# IronSAMD51.net
KiCad netlist of a schematic drawn in EAGLE
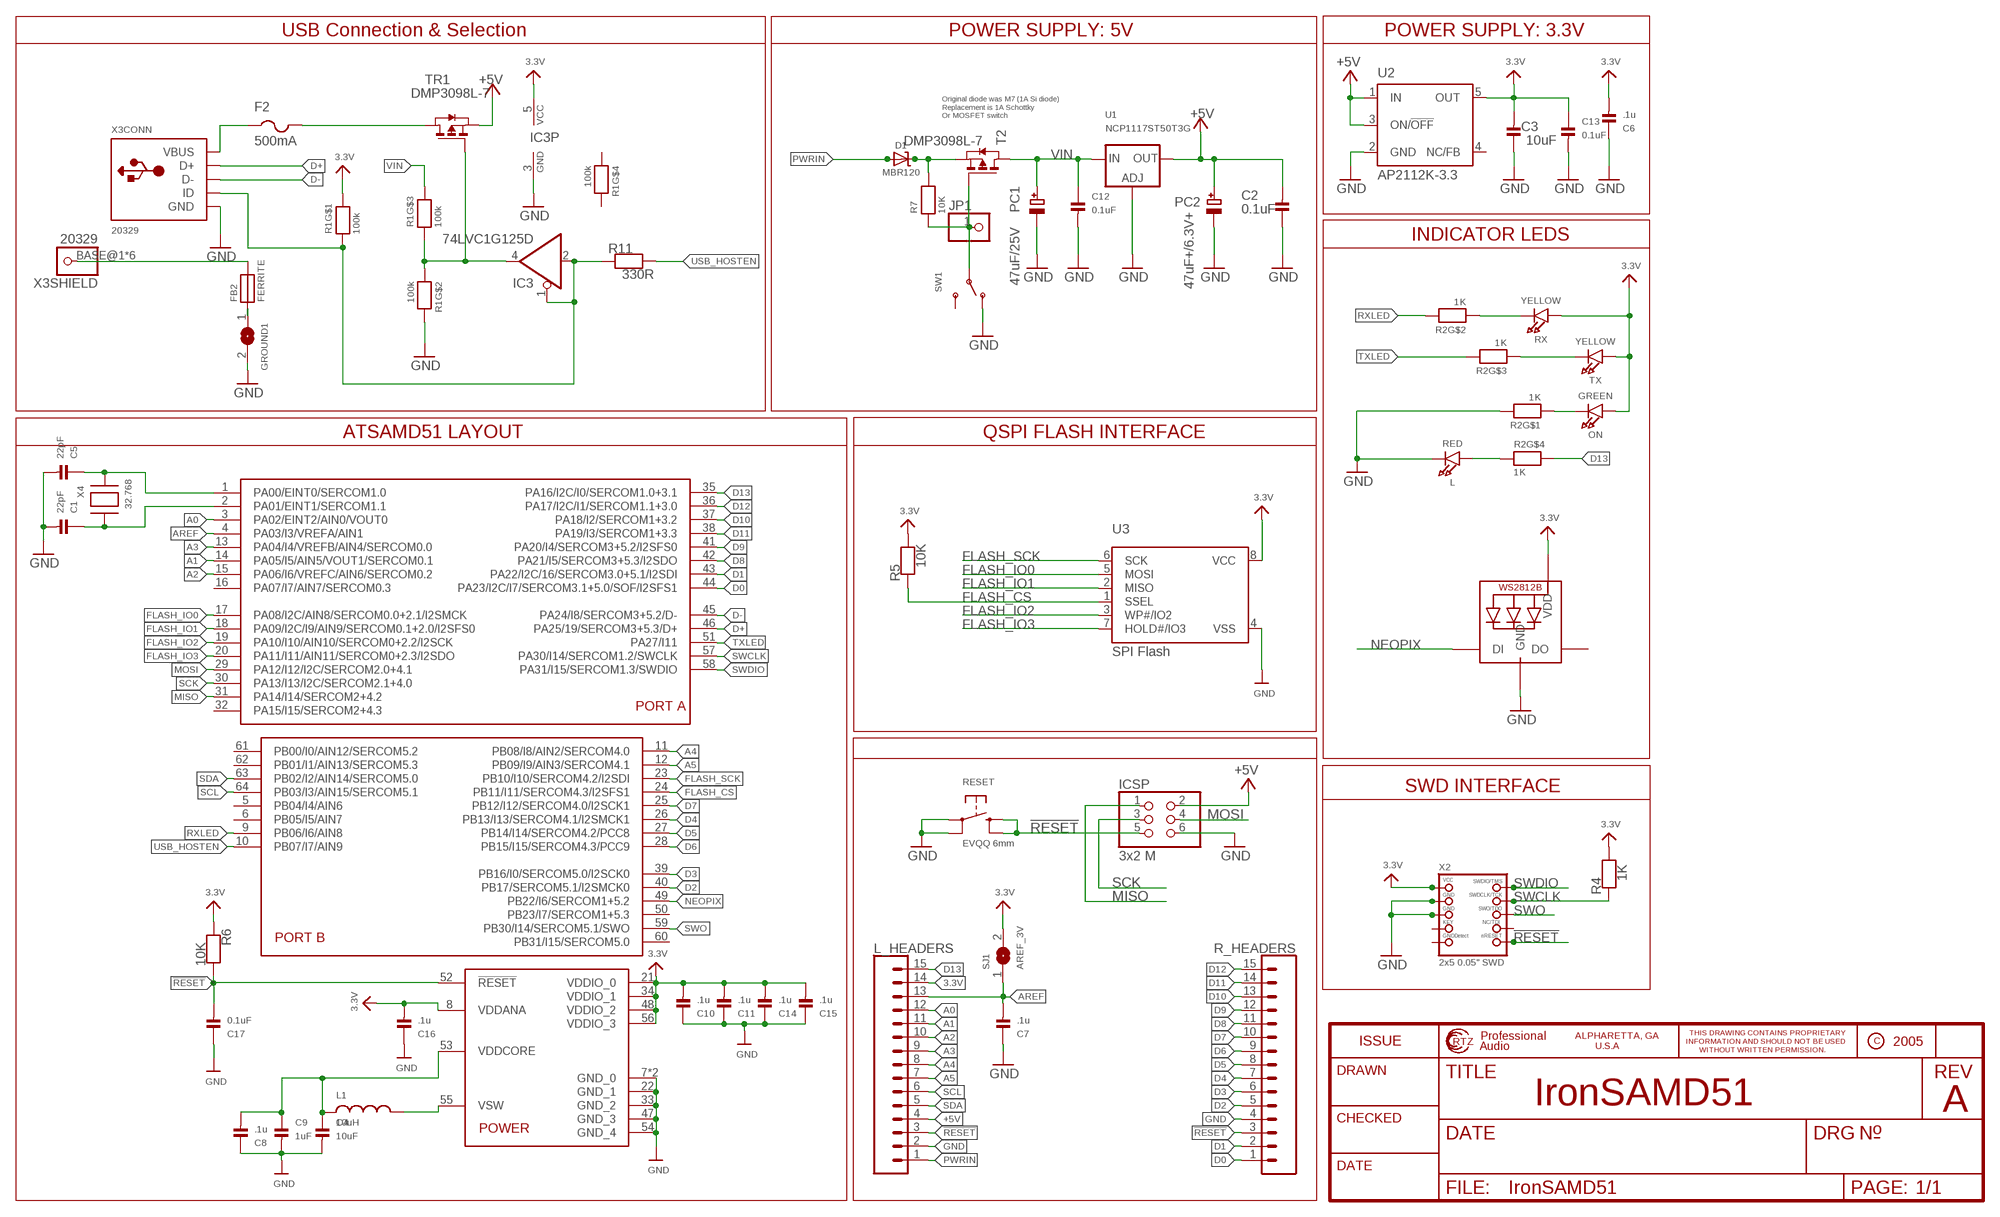
[diagram p0: schematic, sheet 1]

(export (version "E")
  (design (tool "Eeschema 10.0.6"))
  (components
    (comp (ref "C1")
      (value "22pF")
      (footprint "eagle-import:0603")
      (libsource (lib "eagle-import") (part "CAP_CERAMIC0603"))
    )
    (comp (ref "C2")
      (value "0.1uF")
      (footprint "eagle-import:0805")
      (libsource (lib "eagle-import") (part "CAP_CERAMIC0805"))
    )
    (comp (ref "C3")
      (value "10uF")
      (footprint "eagle-import:0805")
      (libsource (lib "eagle-import") (part "CAP_CERAMIC0805"))
    )
    (comp (ref "C4")
      (value "10uF")
      (footprint "eagle-import:0805")
      (libsource (lib "eagle-import") (part "CAP_CERAMIC0805"))
    )
    (comp (ref "C5")
      (value "22pF")
      (footprint "eagle-import:0603")
      (libsource (lib "eagle-import") (part "CAP_CERAMIC0603"))
    )
    (comp (ref "C6")
      (value ".1u")
      (footprint "eagle-import:0603")
      (libsource (lib "eagle-import") (part "CAP_CERAMIC0603"))
    )
    (comp (ref "C7")
      (value ".1u")
      (footprint "eagle-import:0603")
      (libsource (lib "eagle-import") (part "CAP_CERAMIC0603"))
    )
    (comp (ref "C8")
      (value ".1u")
      (footprint "eagle-import:0603")
      (libsource (lib "eagle-import") (part "CAP_CERAMIC0603"))
    )
    (comp (ref "C9")
      (value "1uF")
      (footprint "eagle-import:0603")
      (libsource (lib "eagle-import") (part "CAP_CERAMIC0603"))
    )
    (comp (ref "C10")
      (value ".1u")
      (footprint "eagle-import:0603")
      (libsource (lib "eagle-import") (part "CAP_CERAMIC0603"))
    )
    (comp (ref "C11")
      (value ".1u")
      (footprint "eagle-import:0603")
      (libsource (lib "eagle-import") (part "CAP_CERAMIC0603"))
    )
    (comp (ref "C12")
      (value "0.1uF")
      (footprint "eagle-import:0603")
      (libsource (lib "eagle-import") (part "CAP_CERAMIC0603"))
    )
    (comp (ref "C13")
      (value "0.1uF")
      (footprint "eagle-import:0603")
      (libsource (lib "eagle-import") (part "CAP_CERAMIC0603"))
    )
    (comp (ref "C14")
      (value ".1u")
      (footprint "eagle-import:0603")
      (libsource (lib "eagle-import") (part "CAP_CERAMIC0603"))
    )
    (comp (ref "C15")
      (value ".1u")
      (footprint "eagle-import:0603")
      (libsource (lib "eagle-import") (part "CAP_CERAMIC0603"))
    )
    (comp (ref "C16")
      (value ".1u")
      (footprint "eagle-import:0603")
      (libsource (lib "eagle-import") (part "CAP_CERAMIC0603"))
    )
    (comp (ref "C17")
      (value "0.1uF")
      (footprint "eagle-import:0603")
      (libsource (lib "eagle-import") (part "CAP_CERAMIC0603"))
    )
    (comp (ref "D1")
      (value "MBR120")
      (footprint "eagle-import:SOD-123")
      (libsource (lib "eagle-import") (part "DIODE-SCHOTTKYSOD-123"))
    )
    (comp (ref "F2")
      (value "500mA")
      (footprint "eagle-import:R1206")
      (libsource (lib "eagle-import") (part "PTCFUSE-1206"))
    )
    (comp (ref "FB2")
      (value "FERRITE")
      (footprint "eagle-import:0603")
      (libsource (lib "eagle-import") (part "FERRITE"))
    )
    (comp (ref "GROUND1")
      (value "SOLDERJUMPERCLOSED")
      (footprint "eagle-import:SOLDERJUMPER_CLOSEDWIRE")
      (libsource (lib "eagle-import") (part "SOLDERJUMPERCLOSED"))
    )
    (comp (ref "IC3")
      (value "74LVC1G125D")
      (footprint "eagle-import:SOT23-5")
      (libsource (lib "eagle-import") (part "741G125DBVAHC"))
    )
    (comp (ref "ICSP")
      (value "3x2 M")
      (footprint "eagle-import:2X03_ROUND_70MIL")
      (libsource (lib "eagle-import") (part "HEADER-2X3"))
    )
    (comp (ref "JP1")
      (value "HEADER-1X1ROUND")
      (footprint "eagle-import:1X01_ROUND")
      (libsource (lib "eagle-import") (part "HEADER-1X1ROUND"))
    )
    (comp (ref "L")
      (value "RED")
      (footprint "eagle-import:CHIPLED_0805_NOOUTLINE")
      (libsource (lib "eagle-import") (part "LED0805_NOOUTLINE"))
    )
    (comp (ref "L1")
      (value "10uH")
      (footprint "eagle-import:INDUCTOR_1007")
      (libsource (lib "eagle-import") (part "INDUCTOR"))
    )
    (comp (ref "LED1")
      (value "WS2812B3535")
      (footprint "eagle-import:LED3535")
      (libsource (lib "eagle-import") (part "WS2812B3535"))
    )
    (comp (ref "L_HEADERS")
      (value "CONN_15")
      (footprint "eagle-import:1X15")
      (libsource (lib "eagle-import") (part "CONN_15"))
    )
    (comp (ref "ON")
      (value "GREEN")
      (footprint "eagle-import:CHIPLED_0805_NOOUTLINE")
      (libsource (lib "eagle-import") (part "LED0805_NOOUTLINE"))
    )
    (comp (ref "PC1")
      (value "47uF/25V")
      (footprint "eagle-import:PANASONIC_D")
      (libsource (lib "eagle-import") (part "CAP_ELECTROLYTICPANASONIC_D"))
    )
    (comp (ref "PC2")
      (value "47uF+/6.3V+")
      (footprint "eagle-import:PANASONIC_D")
      (libsource (lib "eagle-import") (part "CAP_ELECTROLYTICPANASONIC_D"))
    )
    (comp (ref "R1")
      (value "100k")
      (footprint "eagle-import:RESPACK_4X0603")
      (libsource (lib "eagle-import") (part "RESISTOR_4PACK"))
    )
    (comp (ref "R2")
      (value "1K")
      (footprint "eagle-import:RESPACK_4X0603")
      (libsource (lib "eagle-import") (part "RESISTOR_4PACK"))
    )
    (comp (ref "R4")
      (value "1K")
      (footprint "eagle-import:0603")
      (libsource (lib "eagle-import") (part "RESISTOR0603"))
    )
    (comp (ref "R5")
      (value "10K")
      (footprint "eagle-import:0603")
      (libsource (lib "eagle-import") (part "RESISTOR0603"))
    )
    (comp (ref "R6")
      (value "10K")
      (footprint "eagle-import:0603")
      (libsource (lib "eagle-import") (part "RESISTOR0603"))
    )
    (comp (ref "R7")
      (value "10K")
      (footprint "eagle-import:0603")
      (libsource (lib "eagle-import") (part "RESISTOR0603"))
    )
    (comp (ref "R11")
      (value "330R")
      (footprint "eagle-import:0603")
      (libsource (lib "eagle-import") (part "RESISTOR0603"))
    )
    (comp (ref "RESET")
      (value "EVQQ 6mm")
      (footprint "eagle-import:EVQ-Q2")
      (libsource (lib "eagle-import") (part "SWITCH_TACT_SMT"))
    )
    (comp (ref "RX")
      (value "YELLOW")
      (footprint "eagle-import:CHIPLED_0805_NOOUTLINE")
      (libsource (lib "eagle-import") (part "LED0805_NOOUTLINE"))
    )
    (comp (ref "R_HEADERS")
      (value "CONN_15")
      (footprint "eagle-import:1X15")
      (libsource (lib "eagle-import") (part "CONN_15"))
    )
    (comp (ref "SJ1")
      (value "AREF_3V")
      (footprint "eagle-import:SOLDERJUMPER_CLOSEDWIRE")
      (libsource (lib "eagle-import") (part "SOLDERJUMPERCLOSED"))
    )
    (comp (ref "SW1")
      (value "SWITCH_SPDT")
      (footprint "eagle-import:SPDT_SMT_SSSS811101")
      (libsource (lib "eagle-import") (part "SWITCH_SPDT"))
    )
    (comp (ref "T2")
      (value "DMP3098L-7")
      (footprint "eagle-import:SOT-23")
      (libsource (lib "eagle-import") (part "PMOSSOT23"))
    )
    (comp (ref "TR1")
      (value "DMP3098L-7")
      (footprint "eagle-import:SOT-23")
      (fields (field (name "PART_NUMBER") "PMV48XP"))
      (libsource (lib "eagle-import") (part "0297_PMV48XP"))
    )
    (comp (ref "TX")
      (value "YELLOW")
      (footprint "eagle-import:CHIPLED_0805_NOOUTLINE")
      (libsource (lib "eagle-import") (part "LED0805_NOOUTLINE"))
    )
    (comp (ref "U$3")
      (value "ATSAMD51J")
      (footprint "eagle-import:PQFN64-1")
      (libsource (lib "eagle-import") (part "ATSAMD51J"))
    )
    (comp (ref "U1")
      (value "NCP1117ST50T3G")
      (footprint "eagle-import:SOT223-R")
      (libsource (lib "eagle-import") (part "LM1117SOT223-REFLOW"))
    )
    (comp (ref "U2")
      (value "AP2112K-3.3")
      (footprint "eagle-import:SOT23-DBV")
      (libsource (lib "eagle-import") (part "LP2985-XXDBVR33"))
    )
    (comp (ref "U3")
      (value "SPI Flash")
      (footprint "eagle-import:SOIC8_208MIL")
      (libsource (lib "eagle-import") (part "SPIFLASH_SOIC8208MIL"))
    )
    (comp (ref "X2")
      (value "2x5 0.05\" SWD")
      (footprint "eagle-import:2X05_1.27MM_BOX_POSTS")
      (libsource (lib "eagle-import") (part "JTAG-CORTEXBOXPOSTS"))
    )
    (comp (ref "X3")
      (value "20329")
      (footprint "eagle-import:4UCONN_20329_V2")
      (libsource (lib "eagle-import") (part "USB_W_SHIELD_V2"))
    )
    (comp (ref "X4")
      (value "32.768")
      (footprint "eagle-import:XTAL3215")
      (libsource (lib "eagle-import") (part "XTAL-3.2X1.5"))
    )
  )
  (nets
    (net (code "1") (name "+5V") (class "Default")
      (node (ref "C2") (pin "2") (pinfunction "P$2_2") (pintype "passive"))
      (node (ref "ICSP") (pin "2") (pinfunction "2_2") (pintype "passive"))
      (node (ref "L_HEADERS") (pin "4") (pinfunction "4_4") (pintype "passive"))
      (node (ref "PC2") (pin "+") (pinfunction "+_+") (pintype "passive"))
      (node (ref "TR1") (pin "2") (pinfunction "S_2") (pintype "passive"))
      (node (ref "U1") (pin "2") (pinfunction "OUT_2") (pintype "passive"))
      (node (ref "U1") (pin "4") (pinfunction "OUT_4") (pintype "passive"))
      (node (ref "U2") (pin "1") (pinfunction "IN_1") (pintype "input"))
      (node (ref "U2") (pin "3") (pinfunction "ON/~{OFF}_3") (pintype "input"))
    )
    (net (code "2") (name "/~{RESET}") (class "Default")
      (node (ref "C17") (pin "2") (pinfunction "P$2_2") (pintype "passive"))
      (node (ref "ICSP") (pin "5") (pinfunction "5_5") (pintype "passive"))
      (node (ref "L_HEADERS") (pin "3") (pinfunction "3_3") (pintype "passive"))
      (node (ref "R6") (pin "2") (pinfunction "2_2") (pintype "passive"))
      (node (ref "RESET") (pin "B") (pinfunction "S_B") (pintype "passive"))
      (node (ref "RESET") (pin "B'") (pinfunction "S1_B'") (pintype "passive"))
      (node (ref "R_HEADERS") (pin "3") (pinfunction "3_3") (pintype "passive"))
      (node (ref "U$3") (pin "52") (pinfunction "~{RESET}_52") (pintype "bidirectional"))
      (node (ref "X2") (pin "10") (pinfunction "NRESET_10") (pintype "bidirectional"))
    )
    (net (code "3") (name "3.3V") (class "Default")
      (node (ref "C10") (pin "2") (pinfunction "P$2_2") (pintype "passive"))
      (node (ref "C11") (pin "2") (pinfunction "P$2_2") (pintype "passive"))
      (node (ref "C13") (pin "1") (pinfunction "P$1_1") (pintype "passive"))
      (node (ref "C14") (pin "2") (pinfunction "P$2_2") (pintype "passive"))
      (node (ref "C15") (pin "2") (pinfunction "P$2_2") (pintype "passive"))
      (node (ref "C16") (pin "2") (pinfunction "P$2_2") (pintype "passive"))
      (node (ref "C3") (pin "2") (pinfunction "P$2_2") (pintype "passive"))
      (node (ref "C6") (pin "2") (pinfunction "P$2_2") (pintype "passive"))
      (node (ref "IC3") (pin "5") (pinfunction "VCC_5") (pintype "power_in"))
      (node (ref "LED1") (pin "2") (pinfunction "VDD_2") (pintype "power_in"))
      (node (ref "L_HEADERS") (pin "14") (pinfunction "14_14") (pintype "passive"))
      (node (ref "ON") (pin "A") (pinfunction "A_A") (pintype "passive"))
      (node (ref "R1") (pin "8") (pinfunction "2_8") (pintype "passive"))
      (node (ref "R4") (pin "2") (pinfunction "2_2") (pintype "passive"))
      (node (ref "R5") (pin "2") (pinfunction "2_2") (pintype "passive"))
      (node (ref "R6") (pin "1") (pinfunction "1_1") (pintype "passive"))
      (node (ref "RX") (pin "A") (pinfunction "A_A") (pintype "passive"))
      (node (ref "SJ1") (pin "2") (pinfunction "2_2") (pintype "passive"))
      (node (ref "TX") (pin "A") (pinfunction "A_A") (pintype "passive"))
      (node (ref "U$3") (pin "21") (pinfunction "VDDIO_0_21") (pintype "bidirectional"))
      (node (ref "U$3") (pin "34") (pinfunction "VDDIO_1_34") (pintype "bidirectional"))
      (node (ref "U$3") (pin "48") (pinfunction "VDDIO_2_48") (pintype "bidirectional"))
      (node (ref "U$3") (pin "56") (pinfunction "VDDIO_3_56") (pintype "bidirectional"))
      (node (ref "U$3") (pin "8") (pinfunction "VDDANA_8") (pintype "bidirectional"))
      (node (ref "U2") (pin "5") (pinfunction "OUT_5") (pintype "passive"))
      (node (ref "U3") (pin "8") (pinfunction "VCC_8") (pintype "bidirectional"))
      (node (ref "X2") (pin "1") (pinfunction "VCC_1") (pintype "power_in"))
    )
    (net (code "4") (name "A0") (class "Default")
      (node (ref "L_HEADERS") (pin "12") (pinfunction "12_12") (pintype "passive"))
      (node (ref "U$3") (pin "3") (pinfunction "PA02/EINT2/AIN0/VOUT0_3") (pintype "bidirectional"))
    )
    (net (code "5") (name "A1") (class "Default")
      (node (ref "L_HEADERS") (pin "11") (pinfunction "11_11") (pintype "passive"))
      (node (ref "U$3") (pin "14") (pinfunction "PA05/I5/AIN5/VOUT1/SERCOM0.1_14") (pintype "bidirectional"))
    )
    (net (code "6") (name "A2") (class "Default")
      (node (ref "L_HEADERS") (pin "10") (pinfunction "10_10") (pintype "passive"))
      (node (ref "U$3") (pin "15") (pinfunction "PA06/I6/VREFC/AIN6/SERCOM0.2_15") (pintype "bidirectional"))
    )
    (net (code "7") (name "A3") (class "Default")
      (node (ref "L_HEADERS") (pin "9") (pinfunction "9_9") (pintype "passive"))
      (node (ref "U$3") (pin "13") (pinfunction "PA04/I4/VREFB/AIN4/SERCOM0.0_13") (pintype "bidirectional"))
    )
    (net (code "8") (name "A4") (class "Default")
      (node (ref "L_HEADERS") (pin "8") (pinfunction "8_8") (pintype "passive"))
      (node (ref "U$3") (pin "11") (pinfunction "PB08/I8/AIN2/SERCOM4.0_11") (pintype "bidirectional"))
    )
    (net (code "9") (name "A5") (class "Default")
      (node (ref "L_HEADERS") (pin "7") (pinfunction "7_7") (pintype "passive"))
      (node (ref "U$3") (pin "12") (pinfunction "PB09/I9/AIN3/SERCOM4.1_12") (pintype "bidirectional"))
    )
    (net (code "10") (name "AREF") (class "Default")
      (node (ref "C7") (pin "2") (pinfunction "P$2_2") (pintype "passive"))
      (node (ref "L_HEADERS") (pin "13") (pinfunction "13_13") (pintype "passive"))
      (node (ref "SJ1") (pin "1") (pinfunction "1_1") (pintype "passive"))
      (node (ref "U$3") (pin "4") (pinfunction "PA03/I3/VREFA/AIN1_4") (pintype "bidirectional"))
    )
    (net (code "11") (name "D+") (class "Default")
      (node (ref "U$3") (pin "46") (pinfunction "PA25/19/SERCOM3+5.3/D+_46") (pintype "bidirectional"))
      (node (ref "X3") (pin "D+") (pinfunction "D+_D+") (pintype "bidirectional"))
    )
    (net (code "12") (name "D-") (class "Default")
      (node (ref "U$3") (pin "45") (pinfunction "PA24/I8/SERCOM3+5.2/D-_45") (pintype "bidirectional"))
      (node (ref "X3") (pin "D-") (pinfunction "D-_D-") (pintype "bidirectional"))
    )
    (net (code "13") (name "D0") (class "Default")
      (node (ref "R_HEADERS") (pin "1") (pinfunction "1_1") (pintype "passive"))
      (node (ref "U$3") (pin "44") (pinfunction "PA23/I2C/I7/SERCOM3.1+5.0/SOF/I2SFS1_44") (pintype "bidirectional"))
    )
    (net (code "14") (name "D1") (class "Default")
      (node (ref "R_HEADERS") (pin "2") (pinfunction "2_2") (pintype "passive"))
      (node (ref "U$3") (pin "43") (pinfunction "PA22/I2C/16/SERCOM3.0+5.1/I2SDI_43") (pintype "bidirectional"))
    )
    (net (code "15") (name "D2") (class "Default")
      (node (ref "R_HEADERS") (pin "5") (pinfunction "5_5") (pintype "passive"))
      (node (ref "U$3") (pin "40") (pinfunction "PB17/SERCOM5.1/I2SMCK0_40") (pintype "bidirectional"))
    )
    (net (code "16") (name "D3") (class "Default")
      (node (ref "R_HEADERS") (pin "6") (pinfunction "6_6") (pintype "passive"))
      (node (ref "U$3") (pin "39") (pinfunction "PB16/I0/SERCOM5.0/I2SCK0_39") (pintype "bidirectional"))
    )
    (net (code "17") (name "D4") (class "Default")
      (node (ref "R_HEADERS") (pin "7") (pinfunction "7_7") (pintype "passive"))
      (node (ref "U$3") (pin "26") (pinfunction "PB13/I13/SERCOM4.1/I2SMCK1_26") (pintype "bidirectional"))
    )
    (net (code "18") (name "D5") (class "Default")
      (node (ref "R_HEADERS") (pin "8") (pinfunction "8_8") (pintype "passive"))
      (node (ref "U$3") (pin "27") (pinfunction "PB14/I14/SERCOM4.2/PCC8_27") (pintype "bidirectional"))
    )
    (net (code "19") (name "D6") (class "Default")
      (node (ref "R_HEADERS") (pin "9") (pinfunction "9_9") (pintype "passive"))
      (node (ref "U$3") (pin "28") (pinfunction "PB15/I15/SERCOM4.3/PCC9_28") (pintype "bidirectional"))
    )
    (net (code "20") (name "D7") (class "Default")
      (node (ref "R_HEADERS") (pin "10") (pinfunction "10_10") (pintype "passive"))
      (node (ref "U$3") (pin "25") (pinfunction "PB12/I12/SERCOM4.0/I2SCK1_25") (pintype "bidirectional"))
    )
    (net (code "21") (name "D8") (class "Default")
      (node (ref "R_HEADERS") (pin "11") (pinfunction "11_11") (pintype "passive"))
      (node (ref "U$3") (pin "42") (pinfunction "PA21/I5/SERCOM3+5.3/I2SDO_42") (pintype "bidirectional"))
    )
    (net (code "22") (name "D9") (class "Default")
      (node (ref "R_HEADERS") (pin "12") (pinfunction "12_12") (pintype "passive"))
      (node (ref "U$3") (pin "41") (pinfunction "PA20/I4/SERCOM3+5.2/I2SFS0_41") (pintype "bidirectional"))
    )
    (net (code "23") (name "D10") (class "Default")
      (node (ref "R_HEADERS") (pin "13") (pinfunction "13_13") (pintype "passive"))
      (node (ref "U$3") (pin "37") (pinfunction "PA18/I2/SERCOM1+3.2_37") (pintype "bidirectional"))
    )
    (net (code "24") (name "D11") (class "Default")
      (node (ref "R_HEADERS") (pin "14") (pinfunction "14_14") (pintype "passive"))
      (node (ref "U$3") (pin "38") (pinfunction "PA19/I3/SERCOM1+3.3_38") (pintype "bidirectional"))
    )
    (net (code "25") (name "D12") (class "Default")
      (node (ref "R_HEADERS") (pin "15") (pinfunction "15_15") (pintype "passive"))
      (node (ref "U$3") (pin "36") (pinfunction "PA17/I2C/I1/SERCOM1.1+3.0_36") (pintype "bidirectional"))
    )
    (net (code "26") (name "D13") (class "Default")
      (node (ref "L_HEADERS") (pin "15") (pinfunction "15_15") (pintype "passive"))
      (node (ref "R2") (pin "5") (pinfunction "2_5") (pintype "passive"))
      (node (ref "U$3") (pin "35") (pinfunction "PA16/I2C/I0/SERCOM1.0+3.1_35") (pintype "bidirectional"))
    )
    (net (code "27") (name "FLASH_CS") (class "Default")
      (node (ref "R5") (pin "1") (pinfunction "1_1") (pintype "passive"))
      (node (ref "U$3") (pin "24") (pinfunction "PB11/I11/SERCOM4.3/I2SFS1_24") (pintype "bidirectional"))
      (node (ref "U3") (pin "1") (pinfunction "SSEL_1") (pintype "bidirectional"))
    )
    (net (code "28") (name "FLASH_IO0") (class "Default")
      (node (ref "U$3") (pin "17") (pinfunction "PA08/I2C/AIN8/SERCOM0.0+2.1/I2SMCK_17") (pintype "bidirectional"))
      (node (ref "U3") (pin "5") (pinfunction "MOSI_5") (pintype "bidirectional"))
    )
    (net (code "29") (name "FLASH_IO1") (class "Default")
      (node (ref "U$3") (pin "18") (pinfunction "PA09/I2C/I9/AIN9/SERCOM0.1+2.0/I2SFS0_18") (pintype "bidirectional"))
      (node (ref "U3") (pin "2") (pinfunction "MISO_2") (pintype "bidirectional"))
    )
    (net (code "30") (name "FLASH_IO2") (class "Default")
      (node (ref "U$3") (pin "19") (pinfunction "PA10/I10/AIN10/SERCOM0+2.2/I2SCK_19") (pintype "bidirectional"))
      (node (ref "U3") (pin "3") (pinfunction "WP#/IO2_3") (pintype "bidirectional"))
    )
    (net (code "31") (name "FLASH_IO3") (class "Default")
      (node (ref "U$3") (pin "20") (pinfunction "PA11/I11/AIN11/SERCOM0+2.3/I2SDO_20") (pintype "bidirectional"))
      (node (ref "U3") (pin "7") (pinfunction "HOLD#/IO3_7") (pintype "bidirectional"))
    )
    (net (code "32") (name "FLASH_SCK") (class "Default")
      (node (ref "U$3") (pin "23") (pinfunction "PB10/I10/SERCOM4.2/I2SDI_23") (pintype "bidirectional"))
      (node (ref "U3") (pin "6") (pinfunction "SCK_6") (pintype "bidirectional"))
    )
    (net (code "33") (name "GND") (class "Default")
      (node (ref "C1") (pin "2") (pinfunction "P$2_2") (pintype "passive"))
      (node (ref "C10") (pin "1") (pinfunction "P$1_1") (pintype "passive"))
      (node (ref "C11") (pin "1") (pinfunction "P$1_1") (pintype "passive"))
      (node (ref "C12") (pin "2") (pinfunction "P$2_2") (pintype "passive"))
      (node (ref "C13") (pin "2") (pinfunction "P$2_2") (pintype "passive"))
      (node (ref "C14") (pin "1") (pinfunction "P$1_1") (pintype "passive"))
      (node (ref "C15") (pin "1") (pinfunction "P$1_1") (pintype "passive"))
      (node (ref "C16") (pin "1") (pinfunction "P$1_1") (pintype "passive"))
      (node (ref "C17") (pin "1") (pinfunction "P$1_1") (pintype "passive"))
      (node (ref "C2") (pin "1") (pinfunction "P$1_1") (pintype "passive"))
      (node (ref "C3") (pin "1") (pinfunction "P$1_1") (pintype "passive"))
      (node (ref "C4") (pin "2") (pinfunction "P$2_2") (pintype "passive"))
      (node (ref "C5") (pin "2") (pinfunction "P$2_2") (pintype "passive"))
      (node (ref "C6") (pin "1") (pinfunction "P$1_1") (pintype "passive"))
      (node (ref "C7") (pin "1") (pinfunction "P$1_1") (pintype "passive"))
      (node (ref "C8") (pin "1") (pinfunction "P$1_1") (pintype "passive"))
      (node (ref "C9") (pin "2") (pinfunction "P$2_2") (pintype "passive"))
      (node (ref "GROUND1") (pin "2") (pinfunction "2_2") (pintype "passive"))
      (node (ref "IC3") (pin "3") (pinfunction "GND_3") (pintype "power_in"))
      (node (ref "ICSP") (pin "6") (pinfunction "6_6") (pintype "passive"))
      (node (ref "L") (pin "C") (pinfunction "C_C") (pintype "passive"))
      (node (ref "LED1") (pin "4") (pinfunction "GND_4") (pintype "power_in"))
      (node (ref "L_HEADERS") (pin "2") (pinfunction "2_2") (pintype "passive"))
      (node (ref "PC1") (pin "-") (pinfunction "-_-") (pintype "passive"))
      (node (ref "PC2") (pin "-") (pinfunction "-_-") (pintype "passive"))
      (node (ref "R1") (pin "7") (pinfunction "2_7") (pintype "passive"))
      (node (ref "R2") (pin "8") (pinfunction "2_8") (pintype "passive"))
      (node (ref "RESET") (pin "A") (pinfunction "P_A") (pintype "passive"))
      (node (ref "RESET") (pin "A'") (pinfunction "P1_A'") (pintype "passive"))
      (node (ref "R_HEADERS") (pin "4") (pinfunction "4_4") (pintype "passive"))
      (node (ref "SW1") (pin "A") (pinfunction "O_A") (pintype "passive"))
      (node (ref "U$3") (pin "22") (pinfunction "GND_1_22") (pintype "bidirectional"))
      (node (ref "U$3") (pin "33") (pinfunction "GND_2_33") (pintype "bidirectional"))
      (node (ref "U$3") (pin "47") (pinfunction "GND_3_47") (pintype "bidirectional"))
      (node (ref "U$3") (pin "54") (pinfunction "GND_4_54") (pintype "bidirectional"))
      (node (ref "U$3") (pin "7") (pinfunction "GND_0_7") (pintype "bidirectional"))
      (node (ref "U$3") (pin "EXP") (pinfunction "GND_0_EXP") (pintype "bidirectional"))
      (node (ref "U1") (pin "1") (pinfunction "ADJ_1") (pintype "input"))
      (node (ref "U2") (pin "2") (pinfunction "GND_2") (pintype "power_in"))
      (node (ref "U3") (pin "4") (pinfunction "VSS_4") (pintype "bidirectional"))
      (node (ref "X2") (pin "3") (pinfunction "GND_3") (pintype "power_in"))
      (node (ref "X2") (pin "5") (pinfunction "GND_5") (pintype "power_in"))
      (node (ref "X3") (pin "GND") (pinfunction "GND_GND") (pintype "power_in"))
    )
    (net (code "34") (name "MISO") (class "Default")
      (node (ref "ICSP") (pin "1") (pinfunction "1_1") (pintype "passive"))
      (node (ref "U$3") (pin "31") (pinfunction "PA14/I14/SERCOM2+4.2_31") (pintype "bidirectional"))
    )
    (net (code "35") (name "MOSI") (class "Default")
      (node (ref "ICSP") (pin "4") (pinfunction "4_4") (pintype "passive"))
      (node (ref "U$3") (pin "29") (pinfunction "PA12/I12/I2C/SERCOM2.0+4.1_29") (pintype "bidirectional"))
    )
    (net (code "36") (name "NEOPIX") (class "Default")
      (node (ref "LED1") (pin "1") (pinfunction "DI_1") (pintype "input"))
      (node (ref "U$3") (pin "49") (pinfunction "PB22/I6/SERCOM1+5.2_49") (pintype "bidirectional"))
    )
    (net (code "37") (name "Net-(C1-P$1)") (class "Default")
      (node (ref "C1") (pin "1") (pinfunction "P$1_1") (pintype "passive"))
      (node (ref "U$3") (pin "2") (pinfunction "PA01/EINT1/SERCOM1.1_2") (pintype "bidirectional"))
      (node (ref "X4") (pin "P$2") (pinfunction "P$2_P$2") (pintype "bidirectional"))
    )
    (net (code "38") (name "Net-(C4-P$1)") (class "Default")
      (node (ref "C4") (pin "1") (pinfunction "P$1_1") (pintype "passive"))
      (node (ref "C8") (pin "2") (pinfunction "P$2_2") (pintype "passive"))
      (node (ref "C9") (pin "1") (pinfunction "P$1_1") (pintype "passive"))
      (node (ref "L1") (pin "P$1") (pinfunction "1_P$1") (pintype "passive"))
      (node (ref "U$3") (pin "53") (pinfunction "VDDCORE_53") (pintype "bidirectional"))
    )
    (net (code "39") (name "Net-(C5-P$1)") (class "Default")
      (node (ref "C5") (pin "1") (pinfunction "P$1_1") (pintype "passive"))
      (node (ref "U$3") (pin "1") (pinfunction "PA00/EINT0/SERCOM1.0_1") (pintype "bidirectional"))
      (node (ref "X4") (pin "P$1") (pinfunction "P$1_P$1") (pintype "bidirectional"))
    )
    (net (code "40") (name "Net-(F2-Pad1)") (class "Default")
      (node (ref "F2") (pin "1") (pinfunction "1_1") (pintype "passive"))
      (node (ref "X3") (pin "VBUS") (pinfunction "VBUS_VBUS") (pintype "power_in"))
    )
    (net (code "41") (name "Net-(FB2-P$1)") (class "Default")
      (node (ref "FB2") (pin "1") (pinfunction "P$1_1") (pintype "bidirectional"))
      (node (ref "GROUND1") (pin "1") (pinfunction "1_1") (pintype "passive"))
    )
    (net (code "42") (name "Net-(FB2-P$2)") (class "Default")
      (node (ref "FB2") (pin "2") (pinfunction "P$2_2") (pintype "bidirectional"))
      (node (ref "X3") (pin "BASE@1") (pinfunction "1_BASE@1") (pintype "passive"))
      (node (ref "X3") (pin "BASE@2") (pinfunction "1_BASE@2") (pintype "passive"))
      (node (ref "X3") (pin "SPRT@1") (pinfunction "1_SPRT@1") (pintype "passive"))
      (node (ref "X3") (pin "SPRT@2") (pinfunction "1_SPRT@2") (pintype "passive"))
      (node (ref "X3") (pin "SPRT@3") (pinfunction "1_SPRT@3") (pintype "passive"))
      (node (ref "X3") (pin "SPRT@4") (pinfunction "1_SPRT@4") (pintype "passive"))
    )
    (net (code "43") (name "Net-(IC3A-I)") (class "Default")
      (node (ref "IC3") (pin "1") (pinfunction "OE_1") (pintype "input"))
      (node (ref "IC3") (pin "2") (pinfunction "I_2") (pintype "input"))
      (node (ref "R1") (pin "1") (pinfunction "1_1") (pintype "passive"))
      (node (ref "R11") (pin "1") (pinfunction "1_1") (pintype "passive"))
      (node (ref "X3") (pin "ID") (pinfunction "ID_ID") (pintype "bidirectional"))
    )
    (net (code "44") (name "Net-(IC3A-O)") (class "Default")
      (node (ref "IC3") (pin "4") (pinfunction "O_4") (pintype "tri_state"))
      (node (ref "R1") (pin "2") (pinfunction "1_2") (pintype "passive"))
      (node (ref "R1") (pin "3") (pinfunction "1_3") (pintype "passive"))
      (node (ref "TR1") (pin "3") (pinfunction "G_3") (pintype "passive"))
    )
    (net (code "45") (name "Net-(L1-2)") (class "Default")
      (node (ref "L1") (pin "P$2") (pinfunction "2_P$2") (pintype "passive"))
      (node (ref "U$3") (pin "55") (pinfunction "VSW_55") (pintype "bidirectional"))
    )
    (net (code "46") (name "Net-(ON-PadC)") (class "Default")
      (node (ref "ON") (pin "C") (pinfunction "C_C") (pintype "passive"))
      (node (ref "R2") (pin "1") (pinfunction "1_1") (pintype "passive"))
    )
    (net (code "47") (name "Net-(R2B-1)") (class "Default")
      (node (ref "R2") (pin "2") (pinfunction "1_2") (pintype "passive"))
      (node (ref "RX") (pin "C") (pinfunction "C_C") (pintype "passive"))
    )
    (net (code "48") (name "Net-(R2C-1)") (class "Default")
      (node (ref "R2") (pin "3") (pinfunction "1_3") (pintype "passive"))
      (node (ref "TX") (pin "C") (pinfunction "C_C") (pintype "passive"))
    )
    (net (code "49") (name "Net-(R2D-1)") (class "Default")
      (node (ref "L") (pin "A") (pinfunction "A_A") (pintype "passive"))
      (node (ref "R2") (pin "4") (pinfunction "1_4") (pintype "passive"))
    )
    (net (code "50") (name "Net-(SW1-P)") (class "Default")
      (node (ref "JP1") (pin "1") (pinfunction "1_1") (pintype "passive"))
      (node (ref "R7") (pin "1") (pinfunction "1_1") (pintype "passive"))
      (node (ref "SW1") (pin "B") (pinfunction "P_B") (pintype "passive"))
      (node (ref "T2") (pin "3") (pinfunction "G_3") (pintype "passive"))
    )
    (net (code "51") (name "Net-(T2-S)") (class "Default")
      (node (ref "D1") (pin "C") (pinfunction "C_C") (pintype "passive"))
      (node (ref "R7") (pin "2") (pinfunction "2_2") (pintype "passive"))
      (node (ref "T2") (pin "2") (pinfunction "S_2") (pintype "passive"))
    )
    (net (code "52") (name "Net-(TR1-D)") (class "Default")
      (node (ref "F2") (pin "2") (pinfunction "2_2") (pintype "passive"))
      (node (ref "TR1") (pin "1") (pinfunction "D_1") (pintype "passive"))
    )
    (net (code "53") (name "PWRIN") (class "Default")
      (node (ref "D1") (pin "A") (pinfunction "A_A") (pintype "passive"))
      (node (ref "L_HEADERS") (pin "1") (pinfunction "1_1") (pintype "passive"))
    )
    (net (code "54") (name "RXLED") (class "Default")
      (node (ref "R2") (pin "7") (pinfunction "2_7") (pintype "passive"))
      (node (ref "U$3") (pin "9") (pinfunction "PB06/I6/AIN8_9") (pintype "bidirectional"))
    )
    (net (code "55") (name "SCK") (class "Default")
      (node (ref "ICSP") (pin "3") (pinfunction "3_3") (pintype "passive"))
      (node (ref "U$3") (pin "30") (pinfunction "PA13/I13/I2C/SERCOM2.1+4.0_30") (pintype "bidirectional"))
    )
    (net (code "56") (name "SCL") (class "Default")
      (node (ref "L_HEADERS") (pin "6") (pinfunction "6_6") (pintype "passive"))
      (node (ref "U$3") (pin "64") (pinfunction "PB03/I3/AIN15/SERCOM5.1_64") (pintype "bidirectional"))
    )
    (net (code "57") (name "SDA") (class "Default")
      (node (ref "L_HEADERS") (pin "5") (pinfunction "5_5") (pintype "passive"))
      (node (ref "U$3") (pin "63") (pinfunction "PB02/I2/AIN14/SERCOM5.0_63") (pintype "bidirectional"))
    )
    (net (code "58") (name "SWCLK") (class "Default")
      (node (ref "R4") (pin "1") (pinfunction "1_1") (pintype "passive"))
      (node (ref "U$3") (pin "57") (pinfunction "PA30/I14/SERCOM1.2/SWCLK_57") (pintype "bidirectional"))
      (node (ref "X2") (pin "4") (pinfunction "SWDCLK_4") (pintype "bidirectional"))
    )
    (net (code "59") (name "SWDIO") (class "Default")
      (node (ref "U$3") (pin "58") (pinfunction "PA31/I15/SERCOM1.3/SWDIO_58") (pintype "bidirectional"))
      (node (ref "X2") (pin "2") (pinfunction "SWDIO_2") (pintype "bidirectional"))
    )
    (net (code "60") (name "SWO") (class "Default")
      (node (ref "U$3") (pin "59") (pinfunction "PB30/I14/SERCOM5.1/SWO_59") (pintype "bidirectional"))
      (node (ref "X2") (pin "6") (pinfunction "SWO_6") (pintype "bidirectional"))
    )
    (net (code "61") (name "TXLED") (class "Default")
      (node (ref "R2") (pin "6") (pinfunction "2_6") (pintype "passive"))
      (node (ref "U$3") (pin "51") (pinfunction "PA27/I11_51") (pintype "bidirectional"))
    )
    (net (code "62") (name "USB_HOSTEN") (class "Default")
      (node (ref "R11") (pin "2") (pinfunction "2_2") (pintype "passive"))
      (node (ref "U$3") (pin "10") (pinfunction "PB07/I7/AIN9_10") (pintype "bidirectional"))
    )
    (net (code "63") (name "VIN") (class "Default")
      (node (ref "C12") (pin "1") (pinfunction "P$1_1") (pintype "passive"))
      (node (ref "PC1") (pin "+") (pinfunction "+_+") (pintype "passive"))
      (node (ref "R1") (pin "6") (pinfunction "2_6") (pintype "passive"))
      (node (ref "T2") (pin "1") (pinfunction "D_1") (pintype "passive"))
      (node (ref "U1") (pin "3") (pinfunction "IN_3") (pintype "input"))
    )
    (net (code "64") (name "unconnected-(LED1-DO-Pad3)") (class "Default")
      (node (ref "LED1") (pin "3") (pinfunction "DO_3") (pintype "output"))
    )
    (net (code "65") (name "unconnected-(R1D-1-Pad4)") (class "Default")
      (node (ref "R1") (pin "4") (pinfunction "1_4") (pintype "passive"))
    )
    (net (code "66") (name "unconnected-(R1D-2-Pad5)") (class "Default")
      (node (ref "R1") (pin "5") (pinfunction "2_5") (pintype "passive"))
    )
    (net (code "67") (name "unconnected-(SW1-S-PadC)") (class "Default")
      (node (ref "SW1") (pin "C") (pinfunction "S_C") (pintype "passive"))
    )
    (net (code "68") (name "unconnected-(U$3A-PA07{slash}I7{slash}AIN7{slash}SERCOM0.3-Pad16)") (class "Default")
      (node (ref "U$3") (pin "16") (pinfunction "PA07/I7/AIN7/SERCOM0.3_16") (pintype "bidirectional"))
    )
    (net (code "69") (name "unconnected-(U$3A-PA15{slash}I15{slash}SERCOM2+4.3-Pad32)") (class "Default")
      (node (ref "U$3") (pin "32") (pinfunction "PA15/I15/SERCOM2+4.3_32") (pintype "bidirectional"))
    )
    (net (code "70") (name "unconnected-(U$3B-PB00{slash}I0{slash}AIN12{slash}SERCOM5.2-Pad61)") (class "Default")
      (node (ref "U$3") (pin "61") (pinfunction "PB00/I0/AIN12/SERCOM5.2_61") (pintype "bidirectional"))
    )
    (net (code "71") (name "unconnected-(U$3B-PB01{slash}I1{slash}AIN13{slash}SERCOM5.3-Pad62)") (class "Default")
      (node (ref "U$3") (pin "62") (pinfunction "PB01/I1/AIN13/SERCOM5.3_62") (pintype "bidirectional"))
    )
    (net (code "72") (name "unconnected-(U$3B-PB04{slash}I4{slash}AIN6-Pad5)") (class "Default")
      (node (ref "U$3") (pin "5") (pinfunction "PB04/I4/AIN6_5") (pintype "bidirectional"))
    )
    (net (code "73") (name "unconnected-(U$3B-PB05{slash}I5{slash}AIN7-Pad6)") (class "Default")
      (node (ref "U$3") (pin "6") (pinfunction "PB05/I5/AIN7_6") (pintype "bidirectional"))
    )
    (net (code "74") (name "unconnected-(U$3B-PB23{slash}I7{slash}SERCOM1+5.3-Pad50)") (class "Default")
      (node (ref "U$3") (pin "50") (pinfunction "PB23/I7/SERCOM1+5.3_50") (pintype "bidirectional"))
    )
    (net (code "75") (name "unconnected-(U$3B-PB31{slash}I15{slash}SERCOM5.0-Pad60)") (class "Default")
      (node (ref "U$3") (pin "60") (pinfunction "PB31/I15/SERCOM5.0_60") (pintype "bidirectional"))
    )
    (net (code "76") (name "unconnected-(U2-NC{slash}FB-Pad4)") (class "Default")
      (node (ref "U2") (pin "4") (pinfunction "NC/FB_4") (pintype "passive"))
    )
    (net (code "77") (name "unconnected-(X2-GNDDETECT-Pad9)") (class "Default")
      (node (ref "X2") (pin "9") (pinfunction "GNDDETECT_9") (pintype "bidirectional"))
    )
    (net (code "78") (name "unconnected-(X2-KEY-Pad7)") (class "Default")
      (node (ref "X2") (pin "7") (pinfunction "KEY_7") (pintype "bidirectional"))
    )
    (net (code "79") (name "unconnected-(X2-TDI-Pad8)") (class "Default")
      (node (ref "X2") (pin "8") (pinfunction "TDI_8") (pintype "bidirectional"))
    )
  )
)
